# Square8.net
KiCad netlist of a schematic drawn in EAGLE
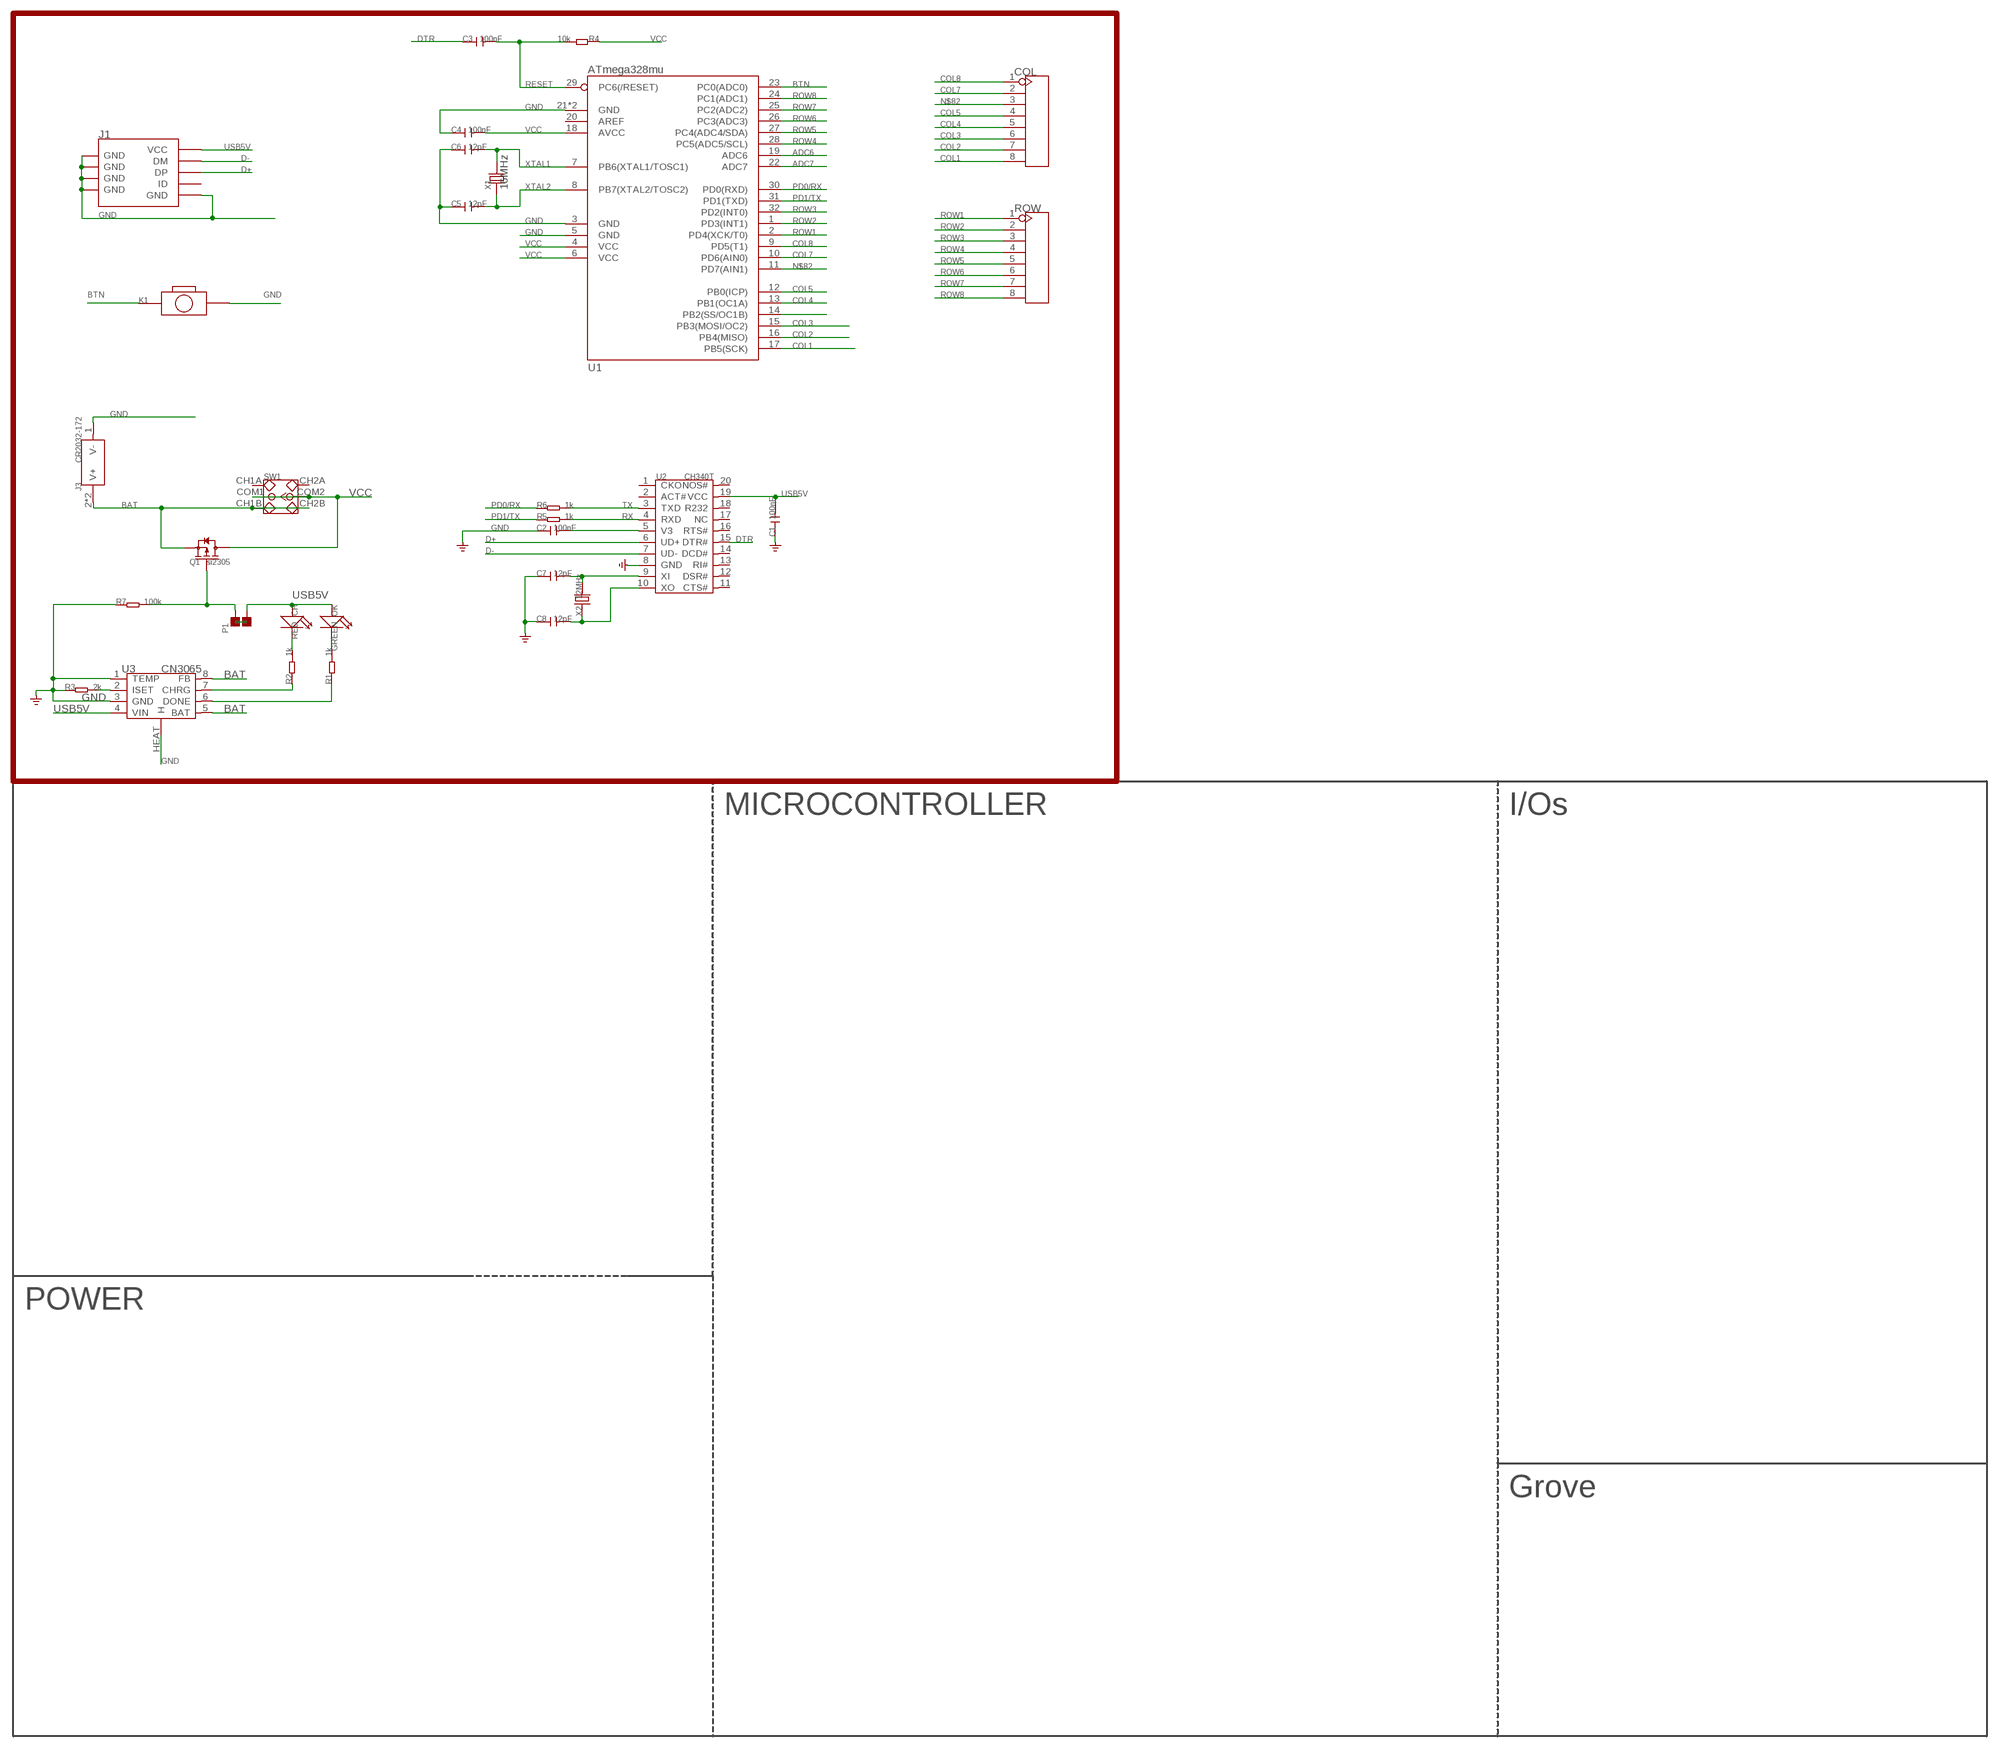
[diagram p0: schematic, sheet 1]

(export (version "E")
  (design (tool "Eeschema 10.0.6"))
  (components
    (comp (ref "C1")
      (value "100nF")
      (footprint "eagle-import:CERAMIC-2.54")
      (libsource (lib "eagle-import") (part "C'2.54'"))
    )
    (comp (ref "C2")
      (value "100nF")
      (footprint "eagle-import:CERAMIC-2.54")
      (libsource (lib "eagle-import") (part "C'2.54'"))
    )
    (comp (ref "C3")
      (value "100nF")
      (footprint "eagle-import:CERAMIC-2.54")
      (libsource (lib "eagle-import") (part "C'2.54'"))
    )
    (comp (ref "C4")
      (value "100nF")
      (footprint "eagle-import:CERAMIC-2.54")
      (libsource (lib "eagle-import") (part "C'2.54'"))
    )
    (comp (ref "C5")
      (value "12pF")
      (footprint "eagle-import:C0603")
      (libsource (lib "eagle-import") (part "C-0603"))
    )
    (comp (ref "C6")
      (value "12pF")
      (footprint "eagle-import:C0603")
      (libsource (lib "eagle-import") (part "C-0603"))
    )
    (comp (ref "C7")
      (value "12pF")
      (footprint "eagle-import:C0603")
      (libsource (lib "eagle-import") (part "C-0603"))
    )
    (comp (ref "C8")
      (value "12pF")
      (footprint "eagle-import:C0603")
      (libsource (lib "eagle-import") (part "C-0603"))
    )
    (comp (ref "CH")
      (value "RED")
      (footprint "eagle-import:LED-2P-2.54-3MM")
      (libsource (lib "eagle-import") (part "LED-3MM"))
    )
    (comp (ref "COL")
      (value "HEADER-8P-2.54")
      (footprint "eagle-import:8P-2.54")
      (libsource (lib "eagle-import") (part "HEADER-8P-2.54"))
    )
    (comp (ref "J1")
      (value "USB-MINIUSB-5P-MICRO")
      (footprint "eagle-import:MICRO-USB")
      (libsource (lib "eagle-import") (part "USB-MINIUSB-5P-MICRO"))
    )
    (comp (ref "J3")
      (value "CR2032-172")
      (footprint "eagle-import:2032-D20-CIRCLE")
      (libsource (lib "eagle-import") (part "HOLDER-BAT-CIRCLE"))
    )
    (comp (ref "K1")
      (value "BUTTON-2P'TS-1101F'")
      (footprint "eagle-import:2P-3.4X6.0X3.55H-90D")
      (libsource (lib "eagle-import") (part "BUTTON-2P'TS-1101F'"))
    )
    (comp (ref "OK")
      (value "GREEN")
      (footprint "eagle-import:LED-2P-2.54-3MM")
      (libsource (lib "eagle-import") (part "LED-3MM"))
    )
    (comp (ref "P1")
      (value "PAD-JUMPER-2P")
      (footprint "eagle-import:2P-SMD-1.78X1.27")
      (fields (field (name "PARTNO") "DNP"))
      (libsource (lib "eagle-import") (part "PAD-JUMPER-2P"))
    )
    (comp (ref "Q1")
      (value "si2305")
      (footprint "eagle-import:SOT23")
      (libsource (lib "eagle-import") (part "MOSFET-P'SI2323CDS/SI2305DS{lt}BR{gt}'"))
    )
    (comp (ref "R1")
      (value "1k")
      (footprint "eagle-import:R0204_7")
      (libsource (lib "eagle-import") (part "R-0204/7"))
    )
    (comp (ref "R2")
      (value "1k")
      (footprint "eagle-import:R0204_7")
      (libsource (lib "eagle-import") (part "R-0204/7"))
    )
    (comp (ref "R3")
      (value "2k")
      (footprint "eagle-import:R0204_7")
      (libsource (lib "eagle-import") (part "R-0204/7"))
    )
    (comp (ref "R4")
      (value "10k")
      (footprint "eagle-import:R0204_7")
      (libsource (lib "eagle-import") (part "R-0204/7"))
    )
    (comp (ref "R5")
      (value "1k")
      (footprint "eagle-import:R0204_7")
      (libsource (lib "eagle-import") (part "R-0204/7"))
    )
    (comp (ref "R6")
      (value "1k")
      (footprint "eagle-import:R0204_7")
      (libsource (lib "eagle-import") (part "R-0204/7"))
    )
    (comp (ref "R7")
      (value "100k")
      (footprint "eagle-import:R0603")
      (libsource (lib "eagle-import") (part "R-0603"))
    )
    (comp (ref "ROW")
      (value "HEADER-8P-2.54")
      (footprint "eagle-import:8P-2.54")
      (libsource (lib "eagle-import") (part "HEADER-8P-2.54"))
    )
    (comp (ref "SW1")
      (value "SWITCH-2CH-6P'90D'")
      (footprint "eagle-import:6P-2CH-2.5-9.1X3.5X3.2H-90D")
      (libsource (lib "eagle-import") (part "SWITCH-2CH-6P'90D'"))
    )
    (comp (ref "U1")
      (value "ATmega328mu")
      (footprint "eagle-import:MLF32X-W_HEAT")
      (libsource (lib "eagle-import") (part "ATMEGA8/168/328MLF"))
    )
    (comp (ref "U2")
      (value "CH340T")
      (footprint "eagle-import:SSOP20")
      (libsource (lib "eagle-import") (part "CH340T"))
    )
    (comp (ref "U3")
      (value "CN3065")
      (footprint "eagle-import:DFN8")
      (libsource (lib "eagle-import") (part "CN3065"))
    )
    (comp (ref "X1")
      (value "16MHz")
      (footprint "eagle-import:HC49S")
      (libsource (lib "eagle-import") (part "CRYSTAL'HC49S'"))
    )
    (comp (ref "X2")
      (value "12MHz")
      (footprint "eagle-import:HC49S")
      (libsource (lib "eagle-import") (part "CRYSTAL'HC49S'"))
    )
  )
  (nets
    (net (code "1") (name "/ADC6") (class "Default")
      (node (ref "U1") (pin "19") (pinfunction "ADC6_19") (pintype "bidirectional"))
    )
    (net (code "2") (name "/ADC7") (class "Default")
      (node (ref "U1") (pin "22") (pinfunction "ADC7_22") (pintype "bidirectional"))
    )
    (net (code "3") (name "/BAT") (class "Default")
      (node (ref "J3") (pin "2") (pinfunction "V+_2") (pintype "bidirectional"))
      (node (ref "J3") (pin "3") (pinfunction "V+_3") (pintype "bidirectional"))
      (node (ref "Q1") (pin "2") (pinfunction "S_2") (pintype "passive"))
      (node (ref "SW1") (pin "CH1B") (pinfunction "CH1B_CH1B") (pintype "bidirectional"))
      (node (ref "SW1") (pin "CH2B") (pinfunction "CH2B_CH2B") (pintype "bidirectional"))
      (node (ref "U3") (pin "5") (pinfunction "BAT_5") (pintype "bidirectional"))
      (node (ref "U3") (pin "8") (pinfunction "FB_8") (pintype "input"))
    )
    (net (code "4") (name "/BTN") (class "Default")
      (node (ref "K1") (pin "P$1") (pinfunction "1_P$1") (pintype "bidirectional"))
      (node (ref "U1") (pin "23") (pinfunction "PC0(ADC0)_23") (pintype "bidirectional"))
    )
    (net (code "5") (name "/COL1") (class "Default")
      (node (ref "COL") (pin "8") (pinfunction "8_8") (pintype "bidirectional"))
      (node (ref "U1") (pin "17") (pinfunction "PB5(SCK)_17") (pintype "bidirectional"))
    )
    (net (code "6") (name "/COL2") (class "Default")
      (node (ref "COL") (pin "7") (pinfunction "7_7") (pintype "bidirectional"))
      (node (ref "U1") (pin "16") (pinfunction "PB4(MISO)_16") (pintype "bidirectional"))
    )
    (net (code "7") (name "/COL3") (class "Default")
      (node (ref "COL") (pin "6") (pinfunction "6_6") (pintype "bidirectional"))
      (node (ref "U1") (pin "15") (pinfunction "PB3(MOSI/OC2)_15") (pintype "bidirectional"))
    )
    (net (code "8") (name "/COL4") (class "Default")
      (node (ref "COL") (pin "5") (pinfunction "5_5") (pintype "bidirectional"))
      (node (ref "U1") (pin "13") (pinfunction "PB1(OC1A)_13") (pintype "bidirectional"))
    )
    (net (code "9") (name "/COL5") (class "Default")
      (node (ref "COL") (pin "4") (pinfunction "4_4") (pintype "bidirectional"))
      (node (ref "U1") (pin "12") (pinfunction "PB0(ICP)_12") (pintype "bidirectional"))
    )
    (net (code "10") (name "/COL7") (class "Default")
      (node (ref "COL") (pin "2") (pinfunction "2_2") (pintype "bidirectional"))
      (node (ref "U1") (pin "10") (pinfunction "PD6(AIN0)_10") (pintype "bidirectional"))
    )
    (net (code "11") (name "/COL8") (class "Default")
      (node (ref "COL") (pin "1") (pinfunction "1_1") (pintype "bidirectional"))
      (node (ref "U1") (pin "9") (pinfunction "PD5(T1)_9") (pintype "bidirectional"))
    )
    (net (code "12") (name "/D+") (class "Default")
      (node (ref "J1") (pin "3") (pinfunction "DP_3") (pintype "bidirectional"))
      (node (ref "U2") (pin "6") (pinfunction "UD+_6") (pintype "bidirectional"))
    )
    (net (code "13") (name "/D-") (class "Default")
      (node (ref "J1") (pin "2") (pinfunction "DM_2") (pintype "bidirectional"))
      (node (ref "U2") (pin "7") (pinfunction "UD-_7") (pintype "bidirectional"))
    )
    (net (code "14") (name "/DTR") (class "Default")
      (node (ref "C3") (pin "1") (pinfunction "1_1") (pintype "passive"))
      (node (ref "U2") (pin "15") (pinfunction "DTR#_15") (pintype "output"))
    )
    (net (code "15") (name "/N$82") (class "Default")
      (node (ref "COL") (pin "3") (pinfunction "3_3") (pintype "bidirectional"))
      (node (ref "U1") (pin "11") (pinfunction "PD7(AIN1)_11") (pintype "bidirectional"))
    )
    (net (code "16") (name "/NOS#") (class "Default")
      (node (ref "U2") (pin "20") (pinfunction "NOS#_20") (pintype "power_in"))
    )
    (net (code "17") (name "/PD0{slash}RX") (class "Default")
      (node (ref "R6") (pin "1") (pinfunction "1_1") (pintype "passive"))
      (node (ref "U1") (pin "30") (pinfunction "PD0(RXD)_30") (pintype "bidirectional"))
    )
    (net (code "18") (name "/PD1{slash}TX") (class "Default")
      (node (ref "R5") (pin "1") (pinfunction "1_1") (pintype "passive"))
      (node (ref "U1") (pin "31") (pinfunction "PD1(TXD)_31") (pintype "bidirectional"))
    )
    (net (code "19") (name "/RESET") (class "Default")
      (node (ref "C3") (pin "2") (pinfunction "2_2") (pintype "passive"))
      (node (ref "R4") (pin "2") (pinfunction "2_2") (pintype "passive"))
      (node (ref "U1") (pin "29") (pinfunction "PC6(/RESET)_29") (pintype "bidirectional"))
    )
    (net (code "20") (name "/ROW1") (class "Default")
      (node (ref "ROW") (pin "1") (pinfunction "1_1") (pintype "bidirectional"))
      (node (ref "U1") (pin "2") (pinfunction "PD4(XCK/T0)_2") (pintype "bidirectional"))
    )
    (net (code "21") (name "/ROW2") (class "Default")
      (node (ref "ROW") (pin "2") (pinfunction "2_2") (pintype "bidirectional"))
      (node (ref "U1") (pin "1") (pinfunction "PD3(INT1)_1") (pintype "bidirectional"))
    )
    (net (code "22") (name "/ROW3") (class "Default")
      (node (ref "ROW") (pin "3") (pinfunction "3_3") (pintype "bidirectional"))
      (node (ref "U1") (pin "32") (pinfunction "PD2(INT0)_32") (pintype "bidirectional"))
    )
    (net (code "23") (name "/ROW4") (class "Default")
      (node (ref "ROW") (pin "4") (pinfunction "4_4") (pintype "bidirectional"))
      (node (ref "U1") (pin "28") (pinfunction "PC5(ADC5/SCL)_28") (pintype "bidirectional"))
    )
    (net (code "24") (name "/ROW5") (class "Default")
      (node (ref "ROW") (pin "5") (pinfunction "5_5") (pintype "bidirectional"))
      (node (ref "U1") (pin "27") (pinfunction "PC4(ADC4/SDA)_27") (pintype "bidirectional"))
    )
    (net (code "25") (name "/ROW6") (class "Default")
      (node (ref "ROW") (pin "6") (pinfunction "6_6") (pintype "bidirectional"))
      (node (ref "U1") (pin "26") (pinfunction "PC3(ADC3)_26") (pintype "bidirectional"))
    )
    (net (code "26") (name "/ROW7") (class "Default")
      (node (ref "ROW") (pin "7") (pinfunction "7_7") (pintype "bidirectional"))
      (node (ref "U1") (pin "25") (pinfunction "PC2(ADC2)_25") (pintype "bidirectional"))
    )
    (net (code "27") (name "/ROW8") (class "Default")
      (node (ref "ROW") (pin "8") (pinfunction "8_8") (pintype "bidirectional"))
      (node (ref "U1") (pin "24") (pinfunction "PC1(ADC1)_24") (pintype "bidirectional"))
    )
    (net (code "28") (name "/RX") (class "Default")
      (node (ref "R5") (pin "2") (pinfunction "2_2") (pintype "passive"))
      (node (ref "U2") (pin "4") (pinfunction "RXD_4") (pintype "input"))
    )
    (net (code "29") (name "/TX") (class "Default")
      (node (ref "R6") (pin "2") (pinfunction "2_2") (pintype "passive"))
      (node (ref "U2") (pin "3") (pinfunction "TXD_3") (pintype "output"))
    )
    (net (code "30") (name "/USB5V") (class "Default")
      (node (ref "C1") (pin "2") (pinfunction "2_2") (pintype "passive"))
      (node (ref "CH") (pin "A") (pinfunction "+_A") (pintype "passive"))
      (node (ref "J1") (pin "1") (pinfunction "VCC_1") (pintype "bidirectional"))
      (node (ref "OK") (pin "A") (pinfunction "+_A") (pintype "passive"))
      (node (ref "P1") (pin "1") (pinfunction "1_1") (pintype "bidirectional"))
      (node (ref "U2") (pin "19") (pinfunction "VCC_19") (pintype "power_in"))
      (node (ref "U3") (pin "4") (pinfunction "VIN_4") (pintype "input"))
    )
    (net (code "31") (name "/VCC") (class "Default")
      (node (ref "C4") (pin "2") (pinfunction "2_2") (pintype "passive"))
      (node (ref "Q1") (pin "3") (pinfunction "D_3") (pintype "passive"))
      (node (ref "R4") (pin "1") (pinfunction "1_1") (pintype "passive"))
      (node (ref "SW1") (pin "COM1") (pinfunction "COM1_COM1") (pintype "bidirectional"))
      (node (ref "SW1") (pin "COM2") (pinfunction "COM2_COM2") (pintype "bidirectional"))
      (node (ref "U1") (pin "18") (pinfunction "AVCC_18") (pintype "bidirectional"))
      (node (ref "U1") (pin "4") (pinfunction "VCC_4") (pintype "bidirectional"))
      (node (ref "U1") (pin "6") (pinfunction "VCC_6") (pintype "bidirectional"))
    )
    (net (code "32") (name "/XTAL1") (class "Default")
      (node (ref "C6") (pin "2") (pinfunction "2_2") (pintype "passive"))
      (node (ref "U1") (pin "7") (pinfunction "PB6(XTAL1/TOSC1)_7") (pintype "bidirectional"))
      (node (ref "X1") (pin "2") (pinfunction "2_2") (pintype "passive"))
    )
    (net (code "33") (name "/XTAL2") (class "Default")
      (node (ref "C5") (pin "2") (pinfunction "2_2") (pintype "passive"))
      (node (ref "U1") (pin "8") (pinfunction "PB7(XTAL2/TOSC2)_8") (pintype "bidirectional"))
      (node (ref "X1") (pin "1") (pinfunction "1_1") (pintype "passive"))
    )
    (net (code "34") (name "GND_POWER") (class "Default")
      (node (ref "C1") (pin "1") (pinfunction "1_1") (pintype "passive"))
      (node (ref "C2") (pin "1") (pinfunction "1_1") (pintype "passive"))
      (node (ref "C4") (pin "1") (pinfunction "1_1") (pintype "passive"))
      (node (ref "C5") (pin "1") (pinfunction "1_1") (pintype "passive"))
      (node (ref "C6") (pin "1") (pinfunction "1_1") (pintype "passive"))
      (node (ref "C7") (pin "1") (pinfunction "1_1") (pintype "passive"))
      (node (ref "C8") (pin "1") (pinfunction "1_1") (pintype "passive"))
      (node (ref "J1") (pin "5") (pinfunction "GND_5") (pintype "bidirectional"))
      (node (ref "J1") (pin "S1") (pinfunction "GND_S1") (pintype "bidirectional"))
      (node (ref "J1") (pin "S2") (pinfunction "GND_S2") (pintype "bidirectional"))
      (node (ref "J1") (pin "S3") (pinfunction "GND_S3") (pintype "bidirectional"))
      (node (ref "J1") (pin "S4") (pinfunction "GND_S4") (pintype "bidirectional"))
      (node (ref "J1") (pin "S5") (pinfunction "GND_S5") (pintype "bidirectional"))
      (node (ref "J1") (pin "S6") (pinfunction "GND_S6") (pintype "bidirectional"))
      (node (ref "J3") (pin "1") (pinfunction "V-_1") (pintype "bidirectional"))
      (node (ref "K1") (pin "P$2") (pinfunction "2_P$2") (pintype "bidirectional"))
      (node (ref "R3") (pin "1") (pinfunction "1_1") (pintype "passive"))
      (node (ref "R7") (pin "1") (pinfunction "1_1") (pintype "passive"))
      (node (ref "U1") (pin "21") (pinfunction "GND_21") (pintype "bidirectional"))
      (node (ref "U1") (pin "3") (pinfunction "GND_3") (pintype "bidirectional"))
      (node (ref "U1") (pin "5") (pinfunction "GND_5") (pintype "bidirectional"))
      (node (ref "U1") (pin "HEAT") (pinfunction "GND_HEAT") (pintype "bidirectional"))
      (node (ref "U2") (pin "8") (pinfunction "GND_8") (pintype "power_in"))
      (node (ref "U3") (pin "1") (pinfunction "TEMP_1") (pintype "input"))
      (node (ref "U3") (pin "3") (pinfunction "GND_3") (pintype "power_in"))
      (node (ref "U3") (pin "HEAT") (pinfunction "H_HEAT") (pintype "bidirectional"))
    )
    (net (code "35") (name "Net-(CH--)") (class "Default")
      (node (ref "CH") (pin "K") (pinfunction "-_K") (pintype "passive"))
      (node (ref "R2") (pin "2") (pinfunction "2_2") (pintype "passive"))
    )
    (net (code "36") (name "Net-(OK--)") (class "Default")
      (node (ref "OK") (pin "K") (pinfunction "-_K") (pintype "passive"))
      (node (ref "R1") (pin "2") (pinfunction "2_2") (pintype "passive"))
    )
    (net (code "37") (name "Net-(Q1-G)") (class "Default")
      (node (ref "P1") (pin "2") (pinfunction "2_2") (pintype "bidirectional"))
      (node (ref "Q1") (pin "1") (pinfunction "G_1") (pintype "passive"))
      (node (ref "R7") (pin "2") (pinfunction "2_2") (pintype "passive"))
    )
    (net (code "38") (name "Net-(U2-V3)") (class "Default")
      (node (ref "C2") (pin "2") (pinfunction "2_2") (pintype "passive"))
      (node (ref "U2") (pin "5") (pinfunction "V3_5") (pintype "power_in"))
    )
    (net (code "39") (name "Net-(U2-XI)") (class "Default")
      (node (ref "C7") (pin "2") (pinfunction "2_2") (pintype "passive"))
      (node (ref "U2") (pin "9") (pinfunction "XI_9") (pintype "input"))
      (node (ref "X2") (pin "2") (pinfunction "2_2") (pintype "passive"))
    )
    (net (code "40") (name "Net-(U2-XO)") (class "Default")
      (node (ref "C8") (pin "2") (pinfunction "2_2") (pintype "passive"))
      (node (ref "U2") (pin "10") (pinfunction "XO_10") (pintype "output"))
      (node (ref "X2") (pin "1") (pinfunction "1_1") (pintype "passive"))
    )
    (net (code "41") (name "Net-(U3-CHRG)") (class "Default")
      (node (ref "R2") (pin "1") (pinfunction "1_1") (pintype "passive"))
      (node (ref "U3") (pin "7") (pinfunction "CHRG_7") (pintype "bidirectional"))
    )
    (net (code "42") (name "Net-(U3-DONE)") (class "Default")
      (node (ref "R1") (pin "1") (pinfunction "1_1") (pintype "passive"))
      (node (ref "U3") (pin "6") (pinfunction "DONE_6") (pintype "bidirectional"))
    )
    (net (code "43") (name "Net-(U3-ISET)") (class "Default")
      (node (ref "R3") (pin "2") (pinfunction "2_2") (pintype "passive"))
      (node (ref "U3") (pin "2") (pinfunction "ISET_2") (pintype "bidirectional"))
    )
    (net (code "44") (name "unconnected-(J1-ID-Pad4)") (class "Default")
      (node (ref "J1") (pin "4") (pinfunction "ID_4") (pintype "bidirectional"))
    )
    (net (code "45") (name "unconnected-(SW1-PadCH1A)") (class "Default")
      (node (ref "SW1") (pin "CH1A") (pinfunction "CH1A_CH1A") (pintype "bidirectional"))
    )
    (net (code "46") (name "unconnected-(SW1-PadCH2A)") (class "Default")
      (node (ref "SW1") (pin "CH2A") (pinfunction "CH2A_CH2A") (pintype "bidirectional"))
    )
    (net (code "47") (name "unconnected-(U1-AREF-Pad20)") (class "Default")
      (node (ref "U1") (pin "20") (pinfunction "AREF_20") (pintype "bidirectional"))
    )
    (net (code "48") (name "unconnected-(U1-PB2(SS{slash}OC1B)-Pad14)") (class "Default")
      (node (ref "U1") (pin "14") (pinfunction "PB2(SS/OC1B)_14") (pintype "bidirectional"))
    )
    (net (code "49") (name "unconnected-(U2-ACT#-Pad2)") (class "Default")
      (node (ref "U2") (pin "2") (pinfunction "ACT#_2") (pintype "output"))
    )
    (net (code "50") (name "unconnected-(U2-CKO-Pad1)") (class "Default")
      (node (ref "U2") (pin "1") (pinfunction "CKO_1") (pintype "output"))
    )
    (net (code "51") (name "unconnected-(U2-CTS#-Pad11)") (class "Default")
      (node (ref "U2") (pin "11") (pinfunction "CTS#_11") (pintype "input"))
    )
    (net (code "52") (name "unconnected-(U2-DCD#-Pad14)") (class "Default")
      (node (ref "U2") (pin "14") (pinfunction "DCD#_14") (pintype "input"))
    )
    (net (code "53") (name "unconnected-(U2-DSR#-Pad12)") (class "Default")
      (node (ref "U2") (pin "12") (pinfunction "DSR#_12") (pintype "input"))
    )
    (net (code "54") (name "unconnected-(U2-NC-Pad17)") (class "Default")
      (node (ref "U2") (pin "17") (pinfunction "NC_17") (pintype "no_connect"))
    )
    (net (code "55") (name "unconnected-(U2-R232-Pad18)") (class "Default")
      (node (ref "U2") (pin "18") (pinfunction "R232_18") (pintype "input"))
    )
    (net (code "56") (name "unconnected-(U2-RI#-Pad13)") (class "Default")
      (node (ref "U2") (pin "13") (pinfunction "RI#_13") (pintype "input"))
    )
    (net (code "57") (name "unconnected-(U2-RTS#-Pad16)") (class "Default")
      (node (ref "U2") (pin "16") (pinfunction "RTS#_16") (pintype "output"))
    )
  )
)
